# fanos.net
KiCad netlist of a schematic drawn in EAGLE
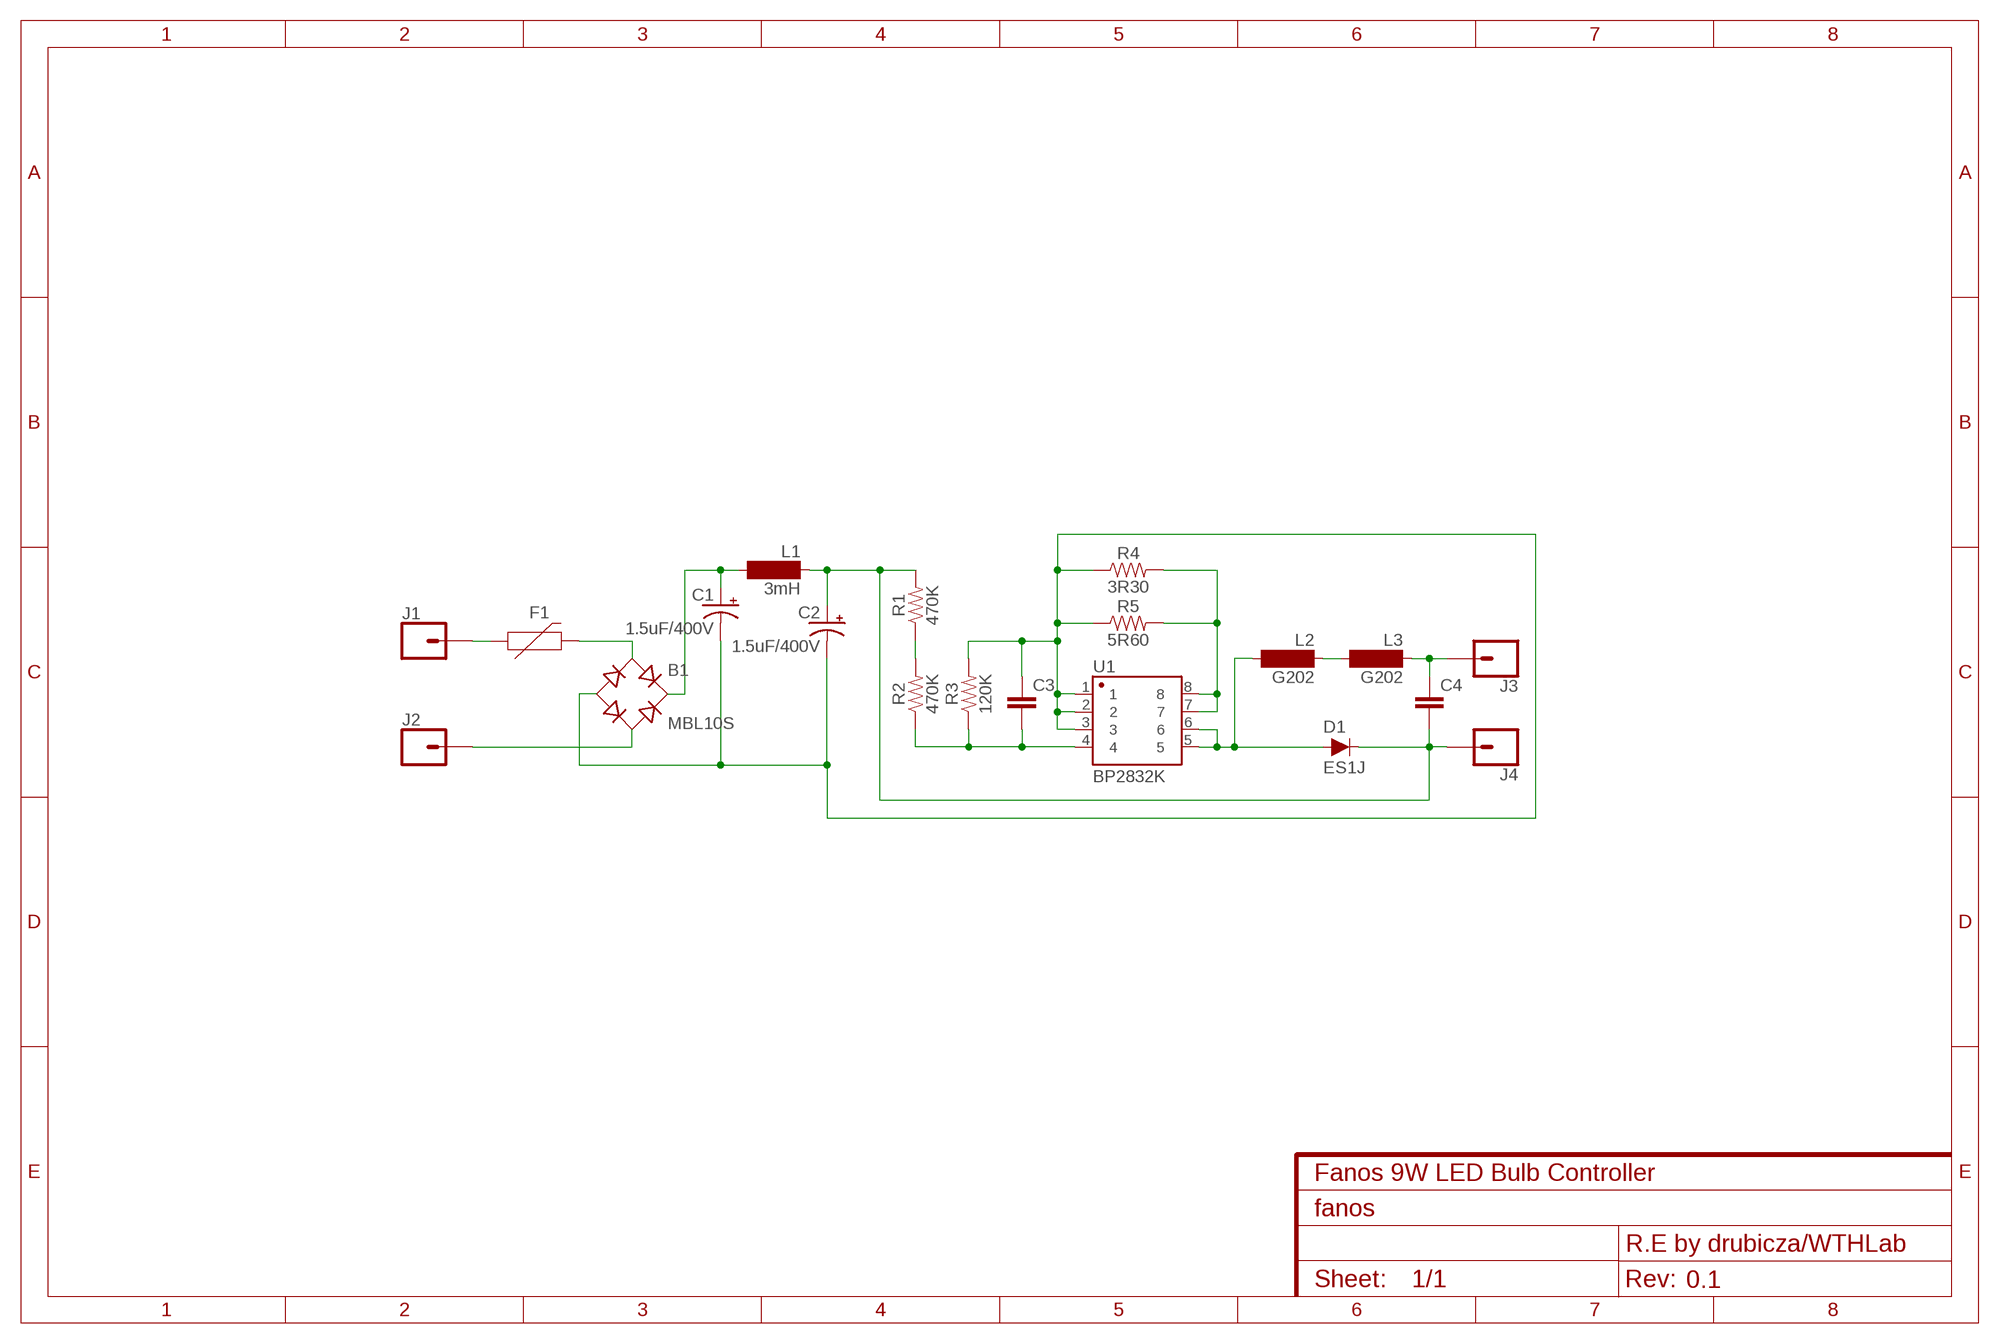
[diagram p0: schematic, sheet 1]

(export (version "E")
  (design (tool "Eeschema 10.0.6"))
  (components
    (comp (ref "B1")
      (value "MBL10S")
      (footprint "eagle-import:SOIC-4")
      (libsource (lib "eagle-import") (part "MBS1"))
    )
    (comp (ref "C1")
      (value "1.5uF/400V")
      (footprint "eagle-import:CPOL-RADIAL-5MM-10MM")
      (libsource (lib "eagle-import") (part "1000UF-RADIAL-5MM-25V-20%"))
    )
    (comp (ref "C2")
      (value "1.5uF/400V")
      (footprint "eagle-import:CPOL-RADIAL-5MM-10MM")
      (libsource (lib "eagle-import") (part "1000UF-RADIAL-5MM-25V-20%"))
    )
    (comp (ref "C3")
      (value "0.18UF-0603-10V-10%")
      (footprint "eagle-import:0603")
      (libsource (lib "eagle-import") (part "0.18UF-0603-10V-10%"))
    )
    (comp (ref "C4")
      (value "0.33UF/330NF-0805-50V-10%")
      (footprint "eagle-import:0805")
      (libsource (lib "eagle-import") (part "0.33UF/330NF-0805-50V-10%"))
    )
    (comp (ref "D1")
      (value "ES1J")
      (footprint "eagle-import:SOD-323")
      (libsource (lib "eagle-import") (part "DIODE-BAS16J"))
    )
    (comp (ref "F1")
      (value "PPTC_PTH")
      (footprint "eagle-import:PTH")
      (libsource (lib "eagle-import") (part "PPTC_PTH"))
    )
    (comp (ref "J1")
      (value "CONN_01")
      (footprint "eagle-import:1X01")
      (libsource (lib "eagle-import") (part "CONN_01"))
    )
    (comp (ref "J2")
      (value "CONN_01")
      (footprint "eagle-import:1X01")
      (libsource (lib "eagle-import") (part "CONN_01"))
    )
    (comp (ref "J3")
      (value "CONN_01")
      (footprint "eagle-import:1X01")
      (libsource (lib "eagle-import") (part "CONN_01"))
    )
    (comp (ref "J4")
      (value "CONN_01")
      (footprint "eagle-import:1X01")
      (libsource (lib "eagle-import") (part "CONN_01"))
    )
    (comp (ref "L1")
      (value "3mH")
      (footprint "eagle-import:BS11")
      (libsource (lib "eagle-import") (part "BS11"))
    )
    (comp (ref "L2")
      (value "G202")
      (footprint "eagle-import:BS11")
      (libsource (lib "eagle-import") (part "BS11"))
    )
    (comp (ref "L3")
      (value "G202")
      (footprint "eagle-import:BS11")
      (libsource (lib "eagle-import") (part "BS11"))
    )
    (comp (ref "R1")
      (value "470K")
      (footprint "eagle-import:0805")
      (libsource (lib "eagle-import") (part "0.3OHM-0805-1/8W-1%"))
    )
    (comp (ref "R2")
      (value "470K")
      (footprint "eagle-import:0805")
      (libsource (lib "eagle-import") (part "0.3OHM-0805-1/8W-1%"))
    )
    (comp (ref "R3")
      (value "120K")
      (footprint "eagle-import:0603")
      (libsource (lib "eagle-import") (part "0.05OHM-0603-1/5W-1%"))
    )
    (comp (ref "R4")
      (value "3R30")
      (footprint "eagle-import:1210")
      (libsource (lib "eagle-import") (part "0.1OHM-1210-1/2W-1%"))
    )
    (comp (ref "R5")
      (value "5R60")
      (footprint "eagle-import:1210")
      (libsource (lib "eagle-import") (part "0.1OHM-1210-1/2W-1%"))
    )
    (comp (ref "U1")
      (value "BP2832K")
      (footprint "eagle-import:SO08")
      (libsource (lib "eagle-import") (part "GENERIC-SOIC8MSGEQ7N-FILTER"))
    )
  )
  (nets
    (net (code "1") (name "Net-(B1-AC1)") (class "Default")
      (node (ref "B1") (pin "~1") (pinfunction "AC1_~1") (pintype "passive"))
      (node (ref "F1") (pin "P$2") (pinfunction "2_P$2") (pintype "bidirectional"))
    )
    (net (code "2") (name "Net-(B1-AC2)") (class "Default")
      (node (ref "B1") (pin "~2") (pinfunction "AC2_~2") (pintype "passive"))
      (node (ref "J2") (pin "1") (pinfunction "1_1") (pintype "passive"))
    )
    (net (code "3") (name "Net-(B1-Pad+)") (class "Default")
      (node (ref "B1") (pin "+") (pinfunction "+_+") (pintype "passive"))
      (node (ref "C1") (pin "+") (pinfunction "+_+") (pintype "passive"))
      (node (ref "L1") (pin "2") (pinfunction "2_2") (pintype "passive"))
    )
    (net (code "4") (name "Net-(B1-Pad-)") (class "Default")
      (node (ref "B1") (pin "-") (pinfunction "-_-") (pintype "passive"))
      (node (ref "C1") (pin "-") (pinfunction "-_-") (pintype "passive"))
      (node (ref "C2") (pin "-") (pinfunction "-_-") (pintype "passive"))
      (node (ref "C3") (pin "1") (pinfunction "1_1") (pintype "passive"))
      (node (ref "R3") (pin "2") (pinfunction "2_2") (pintype "passive"))
      (node (ref "R4") (pin "1") (pinfunction "1_1") (pintype "passive"))
      (node (ref "R5") (pin "1") (pinfunction "1_1") (pintype "passive"))
      (node (ref "U1") (pin "1") (pinfunction "1_1") (pintype "bidirectional"))
      (node (ref "U1") (pin "2") (pinfunction "2_2") (pintype "bidirectional"))
      (node (ref "U1") (pin "3") (pinfunction "3_3") (pintype "bidirectional"))
    )
    (net (code "5") (name "Net-(C2-Pad+)") (class "Default")
      (node (ref "C2") (pin "+") (pinfunction "+_+") (pintype "passive"))
      (node (ref "C4") (pin "2") (pinfunction "2_2") (pintype "passive"))
      (node (ref "D1") (pin "C") (pinfunction "C_C") (pintype "passive"))
      (node (ref "J4") (pin "1") (pinfunction "1_1") (pintype "passive"))
      (node (ref "L1") (pin "1") (pinfunction "1_1") (pintype "passive"))
      (node (ref "R1") (pin "2") (pinfunction "2_2") (pintype "passive"))
    )
    (net (code "6") (name "Net-(C3-Pad2)") (class "Default")
      (node (ref "C3") (pin "2") (pinfunction "2_2") (pintype "passive"))
      (node (ref "R2") (pin "1") (pinfunction "1_1") (pintype "passive"))
      (node (ref "R3") (pin "1") (pinfunction "1_1") (pintype "passive"))
      (node (ref "U1") (pin "4") (pinfunction "4_4") (pintype "bidirectional"))
    )
    (net (code "7") (name "Net-(C4-Pad1)") (class "Default")
      (node (ref "C4") (pin "1") (pinfunction "1_1") (pintype "passive"))
      (node (ref "J3") (pin "1") (pinfunction "1_1") (pintype "passive"))
      (node (ref "L3") (pin "1") (pinfunction "1_1") (pintype "passive"))
    )
    (net (code "8") (name "Net-(D1-PadA)") (class "Default")
      (node (ref "D1") (pin "A") (pinfunction "A_A") (pintype "passive"))
      (node (ref "L2") (pin "2") (pinfunction "2_2") (pintype "passive"))
      (node (ref "U1") (pin "5") (pinfunction "5_5") (pintype "bidirectional"))
      (node (ref "U1") (pin "6") (pinfunction "6_6") (pintype "bidirectional"))
    )
    (net (code "9") (name "Net-(F1-1)") (class "Default")
      (node (ref "F1") (pin "P$1") (pinfunction "1_P$1") (pintype "bidirectional"))
      (node (ref "J1") (pin "1") (pinfunction "1_1") (pintype "passive"))
    )
    (net (code "10") (name "Net-(L2-Pad1)") (class "Default")
      (node (ref "L2") (pin "1") (pinfunction "1_1") (pintype "passive"))
      (node (ref "L3") (pin "2") (pinfunction "2_2") (pintype "passive"))
    )
    (net (code "11") (name "Net-(R1-Pad1)") (class "Default")
      (node (ref "R1") (pin "1") (pinfunction "1_1") (pintype "passive"))
      (node (ref "R2") (pin "2") (pinfunction "2_2") (pintype "passive"))
    )
    (net (code "12") (name "Net-(R4-Pad2)") (class "Default")
      (node (ref "R4") (pin "2") (pinfunction "2_2") (pintype "passive"))
      (node (ref "R5") (pin "2") (pinfunction "2_2") (pintype "passive"))
      (node (ref "U1") (pin "7") (pinfunction "7_7") (pintype "bidirectional"))
      (node (ref "U1") (pin "8") (pinfunction "8_8") (pintype "bidirectional"))
    )
  )
)
